# do1.net
KiCad netlist of a schematic drawn in Altium Designer
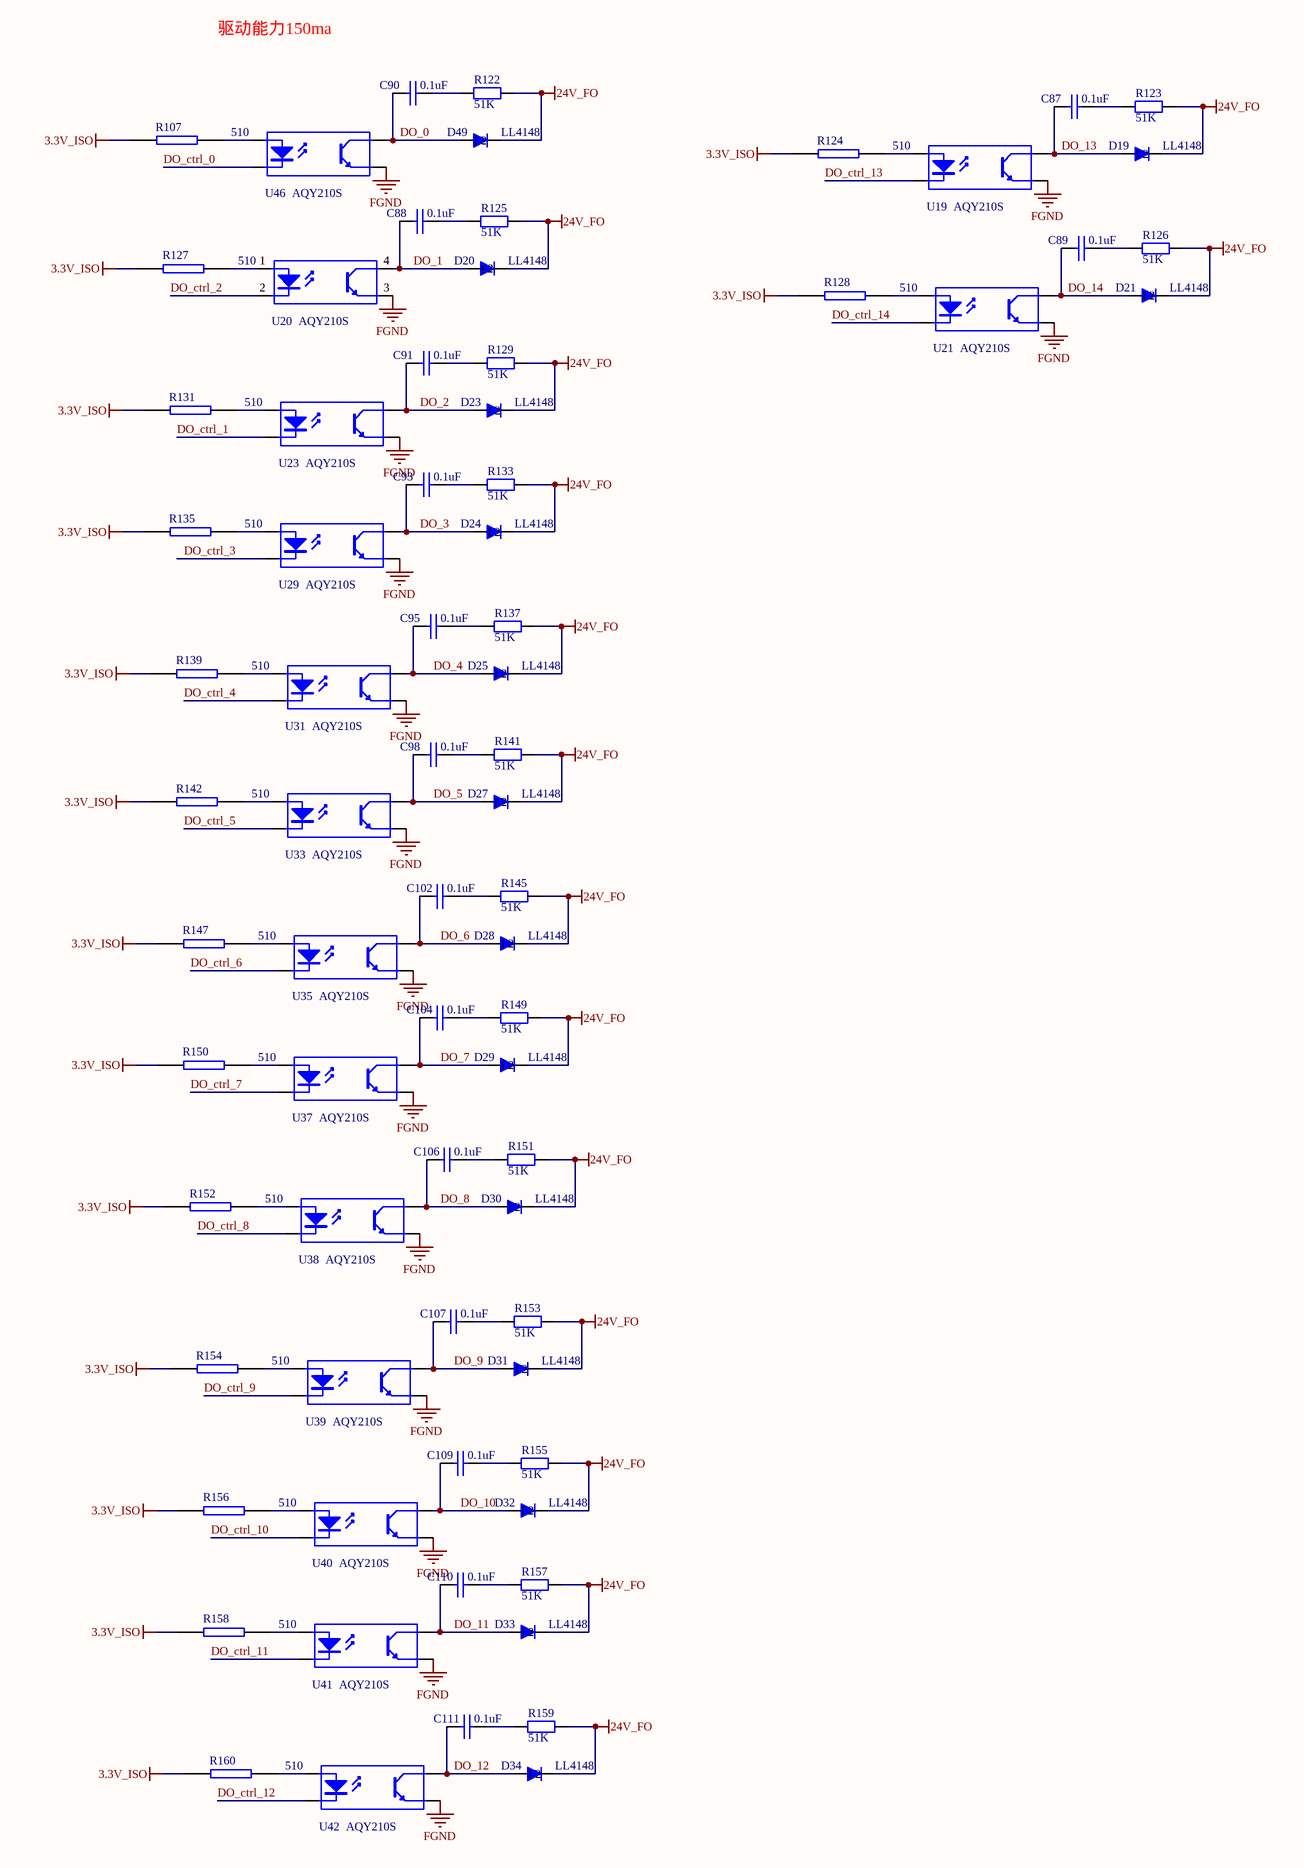
[diagram p0: do1.SchDoc]

(export (version "E")
  (design (tool "Eeschema 10.0.6"))
  (components
    (comp (ref "C87")
      (value "0.1uF")
      (footprint "0603C")
      (description "Capacitor")
      (libsource (lib "*") (part "CAP"))
    )
    (comp (ref "C88")
      (value "0.1uF")
      (footprint "0603C")
      (description "Capacitor")
      (libsource (lib "*") (part "CAP"))
    )
    (comp (ref "C89")
      (value "0.1uF")
      (footprint "0603C")
      (description "Capacitor")
      (libsource (lib "*") (part "CAP"))
    )
    (comp (ref "C90")
      (value "0.1uF")
      (footprint "0603C")
      (description "Capacitor")
      (libsource (lib "*") (part "CAP"))
    )
    (comp (ref "C91")
      (value "0.1uF")
      (footprint "0603C")
      (description "Capacitor")
      (libsource (lib "*") (part "CAP"))
    )
    (comp (ref "C93")
      (value "0.1uF")
      (footprint "0603C")
      (description "Capacitor")
      (libsource (lib "*") (part "CAP"))
    )
    (comp (ref "C95")
      (value "0.1uF")
      (footprint "0603C")
      (description "Capacitor")
      (libsource (lib "*") (part "CAP"))
    )
    (comp (ref "C98")
      (value "0.1uF")
      (footprint "0603C")
      (description "Capacitor")
      (libsource (lib "*") (part "CAP"))
    )
    (comp (ref "C102")
      (value "0.1uF")
      (footprint "0603C")
      (description "Capacitor")
      (libsource (lib "*") (part "CAP"))
    )
    (comp (ref "C104")
      (value "0.1uF")
      (footprint "0603C")
      (description "Capacitor")
      (libsource (lib "*") (part "CAP"))
    )
    (comp (ref "C106")
      (value "0.1uF")
      (footprint "0603C")
      (description "Capacitor")
      (libsource (lib "*") (part "CAP"))
    )
    (comp (ref "C107")
      (value "0.1uF")
      (footprint "0603C")
      (description "Capacitor")
      (libsource (lib "*") (part "CAP"))
    )
    (comp (ref "C109")
      (value "0.1uF")
      (footprint "0603C")
      (description "Capacitor")
      (libsource (lib "*") (part "CAP"))
    )
    (comp (ref "C110")
      (value "0.1uF")
      (footprint "0603C")
      (description "Capacitor")
      (libsource (lib "*") (part "CAP"))
    )
    (comp (ref "C111")
      (value "0.1uF")
      (footprint "0603C")
      (description "Capacitor")
      (libsource (lib "*") (part "CAP"))
    )
    (comp (ref "D19")
      (value "LL4148")
      (footprint "DO-213AB/LL34/MiniMELF")
      (description "VISHAY,LL4148,圆柱体MiniMELF100V/2A,ROHS")
      (libsource (lib "Device2018") (part "LL4148"))
    )
    (comp (ref "D20")
      (value "LL4148")
      (footprint "DO-213AB/LL34/MiniMELF")
      (description "VISHAY,LL4148,圆柱体MiniMELF100V/2A,ROHS")
      (libsource (lib "Device2018") (part "LL4148"))
    )
    (comp (ref "D21")
      (value "LL4148")
      (footprint "DO-213AB/LL34/MiniMELF")
      (description "VISHAY,LL4148,圆柱体MiniMELF100V/2A,ROHS")
      (libsource (lib "Device2018") (part "LL4148"))
    )
    (comp (ref "D23")
      (value "LL4148")
      (footprint "DO-213AB/LL34/MiniMELF")
      (description "VISHAY,LL4148,圆柱体MiniMELF100V/2A,ROHS")
      (libsource (lib "Device2018") (part "LL4148"))
    )
    (comp (ref "D24")
      (value "LL4148")
      (footprint "DO-213AB/LL34/MiniMELF")
      (description "VISHAY,LL4148,圆柱体MiniMELF100V/2A,ROHS")
      (libsource (lib "Device2018") (part "LL4148"))
    )
    (comp (ref "D25")
      (value "LL4148")
      (footprint "DO-213AB/LL34/MiniMELF")
      (description "VISHAY,LL4148,圆柱体MiniMELF100V/2A,ROHS")
      (libsource (lib "Device2018") (part "LL4148"))
    )
    (comp (ref "D27")
      (value "LL4148")
      (footprint "DO-213AB/LL34/MiniMELF")
      (description "VISHAY,LL4148,圆柱体MiniMELF100V/2A,ROHS")
      (libsource (lib "Device2018") (part "LL4148"))
    )
    (comp (ref "D28")
      (value "LL4148")
      (footprint "DO-213AB/LL34/MiniMELF")
      (description "VISHAY,LL4148,圆柱体MiniMELF100V/2A,ROHS")
      (libsource (lib "Device2018") (part "LL4148"))
    )
    (comp (ref "D29")
      (value "LL4148")
      (footprint "DO-213AB/LL34/MiniMELF")
      (description "VISHAY,LL4148,圆柱体MiniMELF100V/2A,ROHS")
      (libsource (lib "Device2018") (part "LL4148"))
    )
    (comp (ref "D30")
      (value "LL4148")
      (footprint "DO-213AB/LL34/MiniMELF")
      (description "VISHAY,LL4148,圆柱体MiniMELF100V/2A,ROHS")
      (libsource (lib "Device2018") (part "LL4148"))
    )
    (comp (ref "D31")
      (value "LL4148")
      (footprint "DO-213AB/LL34/MiniMELF")
      (description "VISHAY,LL4148,圆柱体MiniMELF100V/2A,ROHS")
      (libsource (lib "Device2018") (part "LL4148"))
    )
    (comp (ref "D32")
      (value "LL4148")
      (footprint "DO-213AB/LL34/MiniMELF")
      (description "VISHAY,LL4148,圆柱体MiniMELF100V/2A,ROHS")
      (libsource (lib "Device2018") (part "LL4148"))
    )
    (comp (ref "D33")
      (value "LL4148")
      (footprint "DO-213AB/LL34/MiniMELF")
      (description "VISHAY,LL4148,圆柱体MiniMELF100V/2A,ROHS")
      (libsource (lib "Device2018") (part "LL4148"))
    )
    (comp (ref "D34")
      (value "LL4148")
      (footprint "DO-213AB/LL34/MiniMELF")
      (description "VISHAY,LL4148,圆柱体MiniMELF100V/2A,ROHS")
      (libsource (lib "Device2018") (part "LL4148"))
    )
    (comp (ref "D49")
      (value "LL4148")
      (footprint "DO-213AB/LL34/MiniMELF")
      (description "VISHAY,LL4148,圆柱体MiniMELF100V/2A,ROHS")
      (libsource (lib "Device2018") (part "LL4148"))
    )
    (comp (ref "R107") (value "510") (footprint "0603R") (libsource (lib "*") (part "RES2")))
    (comp (ref "R122") (value "51K") (footprint "0603R") (libsource (lib "MQlibrary") (part "Res0805M")))
    (comp (ref "R123") (value "51K") (footprint "0603R") (libsource (lib "MQlibrary") (part "Res0805M")))
    (comp (ref "R124") (value "510") (footprint "0603R") (libsource (lib "*") (part "RES2")))
    (comp (ref "R125") (value "51K") (footprint "0603R") (libsource (lib "MQlibrary") (part "Res0805M")))
    (comp (ref "R126") (value "51K") (footprint "0603R") (libsource (lib "MQlibrary") (part "Res0805M")))
    (comp (ref "R127") (value "510") (footprint "0603R") (libsource (lib "*") (part "RES2")))
    (comp (ref "R128") (value "510") (footprint "0603R") (libsource (lib "*") (part "RES2")))
    (comp (ref "R129") (value "51K") (footprint "0603R") (libsource (lib "MQlibrary") (part "Res0805M")))
    (comp (ref "R131") (value "510") (footprint "0603R") (libsource (lib "*") (part "RES2")))
    (comp (ref "R133") (value "51K") (footprint "0603R") (libsource (lib "MQlibrary") (part "Res0805M")))
    (comp (ref "R135") (value "510") (footprint "0603R") (libsource (lib "*") (part "RES2")))
    (comp (ref "R137") (value "51K") (footprint "0603R") (libsource (lib "MQlibrary") (part "Res0805M")))
    (comp (ref "R139") (value "510") (footprint "0603R") (libsource (lib "*") (part "RES2")))
    (comp (ref "R141") (value "51K") (footprint "0603R") (libsource (lib "MQlibrary") (part "Res0805M")))
    (comp (ref "R142") (value "510") (footprint "0603R") (libsource (lib "*") (part "RES2")))
    (comp (ref "R145") (value "51K") (footprint "0603R") (libsource (lib "MQlibrary") (part "Res0805M")))
    (comp (ref "R147") (value "510") (footprint "0603R") (libsource (lib "*") (part "RES2")))
    (comp (ref "R149") (value "51K") (footprint "0603R") (libsource (lib "MQlibrary") (part "Res0805M")))
    (comp (ref "R150") (value "510") (footprint "0603R") (libsource (lib "*") (part "RES2")))
    (comp (ref "R151") (value "51K") (footprint "0603R") (libsource (lib "MQlibrary") (part "Res0805M")))
    (comp (ref "R152") (value "510") (footprint "0603R") (libsource (lib "*") (part "RES2")))
    (comp (ref "R153") (value "51K") (footprint "0603R") (libsource (lib "MQlibrary") (part "Res0805M")))
    (comp (ref "R154") (value "510") (footprint "0603R") (libsource (lib "*") (part "RES2")))
    (comp (ref "R155") (value "51K") (footprint "0603R") (libsource (lib "MQlibrary") (part "Res0805M")))
    (comp (ref "R156") (value "510") (footprint "0603R") (libsource (lib "*") (part "RES2")))
    (comp (ref "R157") (value "51K") (footprint "0603R") (libsource (lib "MQlibrary") (part "Res0805M")))
    (comp (ref "R158") (value "510") (footprint "0603R") (libsource (lib "*") (part "RES2")))
    (comp (ref "R159") (value "51K") (footprint "0603R") (libsource (lib "MQlibrary") (part "Res0805M")))
    (comp (ref "R160") (value "510") (footprint "0603R") (libsource (lib "*") (part "RES2")))
    (comp (ref "U19")
      (value "AQY210S")
      (footprint "sop4")
      (description "4-Pin Phototransistor Optocoupler")
      (fields (field (name "PUBLISHER") "Altium Limited"))
      (libsource (lib "") (part "Optoisolator1_1"))
    )
    (comp (ref "U20")
      (value "AQY210S")
      (footprint "sop4")
      (description "4-Pin Phototransistor Optocoupler")
      (fields (field (name "PUBLISHER") "Altium Limited"))
      (libsource (lib "Miscellaneous Devices") (part "Optoisolator1"))
    )
    (comp (ref "U21")
      (value "AQY210S")
      (footprint "sop4")
      (description "4-Pin Phototransistor Optocoupler")
      (fields (field (name "PUBLISHER") "Altium Limited"))
      (libsource (lib "") (part "Optoisolator1_1"))
    )
    (comp (ref "U23")
      (value "AQY210S")
      (footprint "sop4")
      (description "4-Pin Phototransistor Optocoupler")
      (fields (field (name "PUBLISHER") "Altium Limited"))
      (libsource (lib "") (part "Optoisolator1_1"))
    )
    (comp (ref "U29")
      (value "AQY210S")
      (footprint "sop4")
      (description "4-Pin Phototransistor Optocoupler")
      (fields (field (name "PUBLISHER") "Altium Limited"))
      (libsource (lib "") (part "Optoisolator1_1"))
    )
    (comp (ref "U31")
      (value "AQY210S")
      (footprint "sop4")
      (description "4-Pin Phototransistor Optocoupler")
      (fields (field (name "PUBLISHER") "Altium Limited"))
      (libsource (lib "") (part "Optoisolator1_1"))
    )
    (comp (ref "U33")
      (value "AQY210S")
      (footprint "sop4")
      (description "4-Pin Phototransistor Optocoupler")
      (fields (field (name "PUBLISHER") "Altium Limited"))
      (libsource (lib "") (part "Optoisolator1_1"))
    )
    (comp (ref "U35")
      (value "AQY210S")
      (footprint "sop4")
      (description "4-Pin Phototransistor Optocoupler")
      (fields (field (name "PUBLISHER") "Altium Limited"))
      (libsource (lib "") (part "Optoisolator1_1"))
    )
    (comp (ref "U37")
      (value "AQY210S")
      (footprint "sop4")
      (description "4-Pin Phototransistor Optocoupler")
      (fields (field (name "PUBLISHER") "Altium Limited"))
      (libsource (lib "") (part "Optoisolator1_1"))
    )
    (comp (ref "U38")
      (value "AQY210S")
      (footprint "sop4")
      (description "4-Pin Phototransistor Optocoupler")
      (fields (field (name "PUBLISHER") "Altium Limited"))
      (libsource (lib "") (part "Optoisolator1_1"))
    )
    (comp (ref "U39")
      (value "AQY210S")
      (footprint "sop4")
      (description "4-Pin Phototransistor Optocoupler")
      (fields (field (name "PUBLISHER") "Altium Limited"))
      (libsource (lib "") (part "Optoisolator1_1"))
    )
    (comp (ref "U40")
      (value "AQY210S")
      (footprint "sop4")
      (description "4-Pin Phototransistor Optocoupler")
      (fields (field (name "PUBLISHER") "Altium Limited"))
      (libsource (lib "") (part "Optoisolator1_1"))
    )
    (comp (ref "U41")
      (value "AQY210S")
      (footprint "sop4")
      (description "4-Pin Phototransistor Optocoupler")
      (fields (field (name "PUBLISHER") "Altium Limited"))
      (libsource (lib "") (part "Optoisolator1_1"))
    )
    (comp (ref "U42")
      (value "AQY210S")
      (footprint "sop4")
      (description "4-Pin Phototransistor Optocoupler")
      (fields (field (name "PUBLISHER") "Altium Limited"))
      (libsource (lib "") (part "Optoisolator1_1"))
    )
    (comp (ref "U46")
      (value "AQY210S")
      (footprint "sop4")
      (description "4-Pin Phototransistor Optocoupler")
      (fields (field (name "PUBLISHER") "Altium Limited"))
      (libsource (lib "") (part "Optoisolator1_1"))
    )
  )
  (nets
    (net (code "1") (name "/DO_0") (class "Default")
      (node (ref "C90") (pin "1") (pinfunction "1_1") (pintype "passive"))
      (node (ref "D49") (pin "1") (pinfunction "2_1") (pintype "passive"))
      (node (ref "U46") (pin "4") (pinfunction "C_4") (pintype "passive"))
    )
    (net (code "2") (name "/DO_1") (class "Default")
      (node (ref "C88") (pin "1") (pinfunction "1_1") (pintype "passive"))
      (node (ref "D20") (pin "1") (pinfunction "2_1") (pintype "passive"))
      (node (ref "U20") (pin "4") (pinfunction "C_4") (pintype "passive"))
    )
    (net (code "3") (name "/DO_2") (class "Default")
      (node (ref "C91") (pin "1") (pinfunction "1_1") (pintype "passive"))
      (node (ref "D23") (pin "1") (pinfunction "2_1") (pintype "passive"))
      (node (ref "U23") (pin "4") (pinfunction "C_4") (pintype "passive"))
    )
    (net (code "4") (name "/DO_3") (class "Default")
      (node (ref "C93") (pin "1") (pinfunction "1_1") (pintype "passive"))
      (node (ref "D24") (pin "1") (pinfunction "2_1") (pintype "passive"))
      (node (ref "U29") (pin "4") (pinfunction "C_4") (pintype "passive"))
    )
    (net (code "5") (name "/DO_4") (class "Default")
      (node (ref "C95") (pin "1") (pinfunction "1_1") (pintype "passive"))
      (node (ref "D25") (pin "1") (pinfunction "2_1") (pintype "passive"))
      (node (ref "U31") (pin "4") (pinfunction "C_4") (pintype "passive"))
    )
    (net (code "6") (name "/DO_5") (class "Default")
      (node (ref "C98") (pin "1") (pinfunction "1_1") (pintype "passive"))
      (node (ref "D27") (pin "1") (pinfunction "2_1") (pintype "passive"))
      (node (ref "U33") (pin "4") (pinfunction "C_4") (pintype "passive"))
    )
    (net (code "7") (name "/DO_6") (class "Default")
      (node (ref "C102") (pin "1") (pinfunction "1_1") (pintype "passive"))
      (node (ref "D28") (pin "1") (pinfunction "2_1") (pintype "passive"))
      (node (ref "U35") (pin "4") (pinfunction "C_4") (pintype "passive"))
    )
    (net (code "8") (name "/DO_7") (class "Default")
      (node (ref "C104") (pin "1") (pinfunction "1_1") (pintype "passive"))
      (node (ref "D29") (pin "1") (pinfunction "2_1") (pintype "passive"))
      (node (ref "U37") (pin "4") (pinfunction "C_4") (pintype "passive"))
    )
    (net (code "9") (name "/DO_8") (class "Default")
      (node (ref "C106") (pin "1") (pinfunction "1_1") (pintype "passive"))
      (node (ref "D30") (pin "1") (pinfunction "2_1") (pintype "passive"))
      (node (ref "U38") (pin "4") (pinfunction "C_4") (pintype "passive"))
    )
    (net (code "10") (name "/DO_9") (class "Default")
      (node (ref "C107") (pin "1") (pinfunction "1_1") (pintype "passive"))
      (node (ref "D31") (pin "1") (pinfunction "2_1") (pintype "passive"))
      (node (ref "U39") (pin "4") (pinfunction "C_4") (pintype "passive"))
    )
    (net (code "11") (name "/DO_10") (class "Default")
      (node (ref "C109") (pin "1") (pinfunction "1_1") (pintype "passive"))
      (node (ref "D32") (pin "1") (pinfunction "2_1") (pintype "passive"))
      (node (ref "U40") (pin "4") (pinfunction "C_4") (pintype "passive"))
    )
    (net (code "12") (name "/DO_11") (class "Default")
      (node (ref "C110") (pin "1") (pinfunction "1_1") (pintype "passive"))
      (node (ref "D33") (pin "1") (pinfunction "2_1") (pintype "passive"))
      (node (ref "U41") (pin "4") (pinfunction "C_4") (pintype "passive"))
    )
    (net (code "13") (name "/DO_12") (class "Default")
      (node (ref "C111") (pin "1") (pinfunction "1_1") (pintype "passive"))
      (node (ref "D34") (pin "1") (pinfunction "2_1") (pintype "passive"))
      (node (ref "U42") (pin "4") (pinfunction "C_4") (pintype "passive"))
    )
    (net (code "14") (name "/DO_13") (class "Default")
      (node (ref "C87") (pin "1") (pinfunction "1_1") (pintype "passive"))
      (node (ref "D19") (pin "1") (pinfunction "2_1") (pintype "passive"))
      (node (ref "U19") (pin "4") (pinfunction "C_4") (pintype "passive"))
    )
    (net (code "15") (name "/DO_14") (class "Default")
      (node (ref "C89") (pin "1") (pinfunction "1_1") (pintype "passive"))
      (node (ref "D21") (pin "1") (pinfunction "2_1") (pintype "passive"))
      (node (ref "U21") (pin "4") (pinfunction "C_4") (pintype "passive"))
    )
    (net (code "16") (name "/DO_ctrl_0") (class "Default")
      (node (ref "U46") (pin "2") (pinfunction "K_2") (pintype "passive"))
    )
    (net (code "17") (name "/DO_ctrl_1") (class "Default")
      (node (ref "U23") (pin "2") (pinfunction "K_2") (pintype "passive"))
    )
    (net (code "18") (name "/DO_ctrl_2") (class "Default")
      (node (ref "U20") (pin "2") (pinfunction "K_2") (pintype "passive"))
    )
    (net (code "19") (name "/DO_ctrl_3") (class "Default")
      (node (ref "U29") (pin "2") (pinfunction "K_2") (pintype "passive"))
    )
    (net (code "20") (name "/DO_ctrl_4") (class "Default")
      (node (ref "U31") (pin "2") (pinfunction "K_2") (pintype "passive"))
    )
    (net (code "21") (name "/DO_ctrl_5") (class "Default")
      (node (ref "U33") (pin "2") (pinfunction "K_2") (pintype "passive"))
    )
    (net (code "22") (name "/DO_ctrl_6") (class "Default")
      (node (ref "U35") (pin "2") (pinfunction "K_2") (pintype "passive"))
    )
    (net (code "23") (name "/DO_ctrl_7") (class "Default")
      (node (ref "U37") (pin "2") (pinfunction "K_2") (pintype "passive"))
    )
    (net (code "24") (name "/DO_ctrl_8") (class "Default")
      (node (ref "U38") (pin "2") (pinfunction "K_2") (pintype "passive"))
    )
    (net (code "25") (name "/DO_ctrl_9") (class "Default")
      (node (ref "U39") (pin "2") (pinfunction "K_2") (pintype "passive"))
    )
    (net (code "26") (name "/DO_ctrl_10") (class "Default")
      (node (ref "U40") (pin "2") (pinfunction "K_2") (pintype "passive"))
    )
    (net (code "27") (name "/DO_ctrl_11") (class "Default")
      (node (ref "U41") (pin "2") (pinfunction "K_2") (pintype "passive"))
    )
    (net (code "28") (name "/DO_ctrl_12") (class "Default")
      (node (ref "U42") (pin "2") (pinfunction "K_2") (pintype "passive"))
    )
    (net (code "29") (name "/DO_ctrl_13") (class "Default")
      (node (ref "U19") (pin "2") (pinfunction "K_2") (pintype "passive"))
    )
    (net (code "30") (name "/DO_ctrl_14") (class "Default")
      (node (ref "U21") (pin "2") (pinfunction "K_2") (pintype "passive"))
    )
    (net (code "31") (name "3.3V_ISO") (class "Default")
      (node (ref "R107") (pin "2") (pinfunction "2_2") (pintype "passive"))
      (node (ref "R124") (pin "2") (pinfunction "2_2") (pintype "passive"))
      (node (ref "R127") (pin "2") (pinfunction "2_2") (pintype "passive"))
      (node (ref "R128") (pin "2") (pinfunction "2_2") (pintype "passive"))
      (node (ref "R131") (pin "2") (pinfunction "2_2") (pintype "passive"))
      (node (ref "R135") (pin "2") (pinfunction "2_2") (pintype "passive"))
      (node (ref "R139") (pin "2") (pinfunction "2_2") (pintype "passive"))
      (node (ref "R142") (pin "2") (pinfunction "2_2") (pintype "passive"))
      (node (ref "R147") (pin "2") (pinfunction "2_2") (pintype "passive"))
      (node (ref "R150") (pin "2") (pinfunction "2_2") (pintype "passive"))
      (node (ref "R152") (pin "2") (pinfunction "2_2") (pintype "passive"))
      (node (ref "R154") (pin "2") (pinfunction "2_2") (pintype "passive"))
      (node (ref "R156") (pin "2") (pinfunction "2_2") (pintype "passive"))
      (node (ref "R158") (pin "2") (pinfunction "2_2") (pintype "passive"))
      (node (ref "R160") (pin "2") (pinfunction "2_2") (pintype "passive"))
    )
    (net (code "32") (name "24V_FO") (class "Default")
      (node (ref "D19") (pin "2") (pinfunction "1_2") (pintype "passive"))
      (node (ref "D20") (pin "2") (pinfunction "1_2") (pintype "passive"))
      (node (ref "D21") (pin "2") (pinfunction "1_2") (pintype "passive"))
      (node (ref "D23") (pin "2") (pinfunction "1_2") (pintype "passive"))
      (node (ref "D24") (pin "2") (pinfunction "1_2") (pintype "passive"))
      (node (ref "D25") (pin "2") (pinfunction "1_2") (pintype "passive"))
      (node (ref "D27") (pin "2") (pinfunction "1_2") (pintype "passive"))
      (node (ref "D28") (pin "2") (pinfunction "1_2") (pintype "passive"))
      (node (ref "D29") (pin "2") (pinfunction "1_2") (pintype "passive"))
      (node (ref "D30") (pin "2") (pinfunction "1_2") (pintype "passive"))
      (node (ref "D31") (pin "2") (pinfunction "1_2") (pintype "passive"))
      (node (ref "D32") (pin "2") (pinfunction "1_2") (pintype "passive"))
      (node (ref "D33") (pin "2") (pinfunction "1_2") (pintype "passive"))
      (node (ref "D34") (pin "2") (pinfunction "1_2") (pintype "passive"))
      (node (ref "D49") (pin "2") (pinfunction "1_2") (pintype "passive"))
      (node (ref "R122") (pin "2") (pinfunction "2_2") (pintype "passive"))
      (node (ref "R123") (pin "2") (pinfunction "2_2") (pintype "passive"))
      (node (ref "R125") (pin "2") (pinfunction "2_2") (pintype "passive"))
      (node (ref "R126") (pin "2") (pinfunction "2_2") (pintype "passive"))
      (node (ref "R129") (pin "2") (pinfunction "2_2") (pintype "passive"))
      (node (ref "R133") (pin "2") (pinfunction "2_2") (pintype "passive"))
      (node (ref "R137") (pin "2") (pinfunction "2_2") (pintype "passive"))
      (node (ref "R141") (pin "2") (pinfunction "2_2") (pintype "passive"))
      (node (ref "R145") (pin "2") (pinfunction "2_2") (pintype "passive"))
      (node (ref "R149") (pin "2") (pinfunction "2_2") (pintype "passive"))
      (node (ref "R151") (pin "2") (pinfunction "2_2") (pintype "passive"))
      (node (ref "R153") (pin "2") (pinfunction "2_2") (pintype "passive"))
      (node (ref "R155") (pin "2") (pinfunction "2_2") (pintype "passive"))
      (node (ref "R157") (pin "2") (pinfunction "2_2") (pintype "passive"))
      (node (ref "R159") (pin "2") (pinfunction "2_2") (pintype "passive"))
    )
    (net (code "33") (name "FGND") (class "Default")
      (node (ref "U19") (pin "3") (pinfunction "E_3") (pintype "passive"))
      (node (ref "U20") (pin "3") (pinfunction "E_3") (pintype "passive"))
      (node (ref "U21") (pin "3") (pinfunction "E_3") (pintype "passive"))
      (node (ref "U23") (pin "3") (pinfunction "E_3") (pintype "passive"))
      (node (ref "U29") (pin "3") (pinfunction "E_3") (pintype "passive"))
      (node (ref "U31") (pin "3") (pinfunction "E_3") (pintype "passive"))
      (node (ref "U33") (pin "3") (pinfunction "E_3") (pintype "passive"))
      (node (ref "U35") (pin "3") (pinfunction "E_3") (pintype "passive"))
      (node (ref "U37") (pin "3") (pinfunction "E_3") (pintype "passive"))
      (node (ref "U38") (pin "3") (pinfunction "E_3") (pintype "passive"))
      (node (ref "U39") (pin "3") (pinfunction "E_3") (pintype "passive"))
      (node (ref "U40") (pin "3") (pinfunction "E_3") (pintype "passive"))
      (node (ref "U41") (pin "3") (pinfunction "E_3") (pintype "passive"))
      (node (ref "U42") (pin "3") (pinfunction "E_3") (pintype "passive"))
      (node (ref "U46") (pin "3") (pinfunction "E_3") (pintype "passive"))
    )
    (net (code "34") (name "Net-(C87-Pad2)") (class "Default")
      (node (ref "C87") (pin "2") (pinfunction "2_2") (pintype "passive"))
      (node (ref "R123") (pin "1") (pinfunction "1_1") (pintype "passive"))
    )
    (net (code "35") (name "Net-(C88-Pad2)") (class "Default")
      (node (ref "C88") (pin "2") (pinfunction "2_2") (pintype "passive"))
      (node (ref "R125") (pin "1") (pinfunction "1_1") (pintype "passive"))
    )
    (net (code "36") (name "Net-(C89-Pad2)") (class "Default")
      (node (ref "C89") (pin "2") (pinfunction "2_2") (pintype "passive"))
      (node (ref "R126") (pin "1") (pinfunction "1_1") (pintype "passive"))
    )
    (net (code "37") (name "Net-(C90-Pad2)") (class "Default")
      (node (ref "C90") (pin "2") (pinfunction "2_2") (pintype "passive"))
      (node (ref "R122") (pin "1") (pinfunction "1_1") (pintype "passive"))
    )
    (net (code "38") (name "Net-(C91-Pad2)") (class "Default")
      (node (ref "C91") (pin "2") (pinfunction "2_2") (pintype "passive"))
      (node (ref "R129") (pin "1") (pinfunction "1_1") (pintype "passive"))
    )
    (net (code "39") (name "Net-(C93-Pad2)") (class "Default")
      (node (ref "C93") (pin "2") (pinfunction "2_2") (pintype "passive"))
      (node (ref "R133") (pin "1") (pinfunction "1_1") (pintype "passive"))
    )
    (net (code "40") (name "Net-(C95-Pad2)") (class "Default")
      (node (ref "C95") (pin "2") (pinfunction "2_2") (pintype "passive"))
      (node (ref "R137") (pin "1") (pinfunction "1_1") (pintype "passive"))
    )
    (net (code "41") (name "Net-(C98-Pad2)") (class "Default")
      (node (ref "C98") (pin "2") (pinfunction "2_2") (pintype "passive"))
      (node (ref "R141") (pin "1") (pinfunction "1_1") (pintype "passive"))
    )
    (net (code "42") (name "Net-(C102-Pad2)") (class "Default")
      (node (ref "C102") (pin "2") (pinfunction "2_2") (pintype "passive"))
      (node (ref "R145") (pin "1") (pinfunction "1_1") (pintype "passive"))
    )
    (net (code "43") (name "Net-(C104-Pad2)") (class "Default")
      (node (ref "C104") (pin "2") (pinfunction "2_2") (pintype "passive"))
      (node (ref "R149") (pin "1") (pinfunction "1_1") (pintype "passive"))
    )
    (net (code "44") (name "Net-(C106-Pad2)") (class "Default")
      (node (ref "C106") (pin "2") (pinfunction "2_2") (pintype "passive"))
      (node (ref "R151") (pin "1") (pinfunction "1_1") (pintype "passive"))
    )
    (net (code "45") (name "Net-(C107-Pad2)") (class "Default")
      (node (ref "C107") (pin "2") (pinfunction "2_2") (pintype "passive"))
      (node (ref "R153") (pin "1") (pinfunction "1_1") (pintype "passive"))
    )
    (net (code "46") (name "Net-(C109-Pad2)") (class "Default")
      (node (ref "C109") (pin "2") (pinfunction "2_2") (pintype "passive"))
      (node (ref "R155") (pin "1") (pinfunction "1_1") (pintype "passive"))
    )
    (net (code "47") (name "Net-(C110-Pad2)") (class "Default")
      (node (ref "C110") (pin "2") (pinfunction "2_2") (pintype "passive"))
      (node (ref "R157") (pin "1") (pinfunction "1_1") (pintype "passive"))
    )
    (net (code "48") (name "Net-(C111-Pad2)") (class "Default")
      (node (ref "C111") (pin "2") (pinfunction "2_2") (pintype "passive"))
      (node (ref "R159") (pin "1") (pinfunction "1_1") (pintype "passive"))
    )
    (net (code "49") (name "Net-(U19-A)") (class "Default")
      (node (ref "R124") (pin "1") (pinfunction "1_1") (pintype "passive"))
      (node (ref "U19") (pin "1") (pinfunction "A_1") (pintype "passive"))
    )
    (net (code "50") (name "Net-(U20-A)") (class "Default")
      (node (ref "R127") (pin "1") (pinfunction "1_1") (pintype "passive"))
      (node (ref "U20") (pin "1") (pinfunction "A_1") (pintype "passive"))
    )
    (net (code "51") (name "Net-(U21-A)") (class "Default")
      (node (ref "R128") (pin "1") (pinfunction "1_1") (pintype "passive"))
      (node (ref "U21") (pin "1") (pinfunction "A_1") (pintype "passive"))
    )
    (net (code "52") (name "Net-(U23-A)") (class "Default")
      (node (ref "R131") (pin "1") (pinfunction "1_1") (pintype "passive"))
      (node (ref "U23") (pin "1") (pinfunction "A_1") (pintype "passive"))
    )
    (net (code "53") (name "Net-(U29-A)") (class "Default")
      (node (ref "R135") (pin "1") (pinfunction "1_1") (pintype "passive"))
      (node (ref "U29") (pin "1") (pinfunction "A_1") (pintype "passive"))
    )
    (net (code "54") (name "Net-(U31-A)") (class "Default")
      (node (ref "R139") (pin "1") (pinfunction "1_1") (pintype "passive"))
      (node (ref "U31") (pin "1") (pinfunction "A_1") (pintype "passive"))
    )
    (net (code "55") (name "Net-(U33-A)") (class "Default")
      (node (ref "R142") (pin "1") (pinfunction "1_1") (pintype "passive"))
      (node (ref "U33") (pin "1") (pinfunction "A_1") (pintype "passive"))
    )
    (net (code "56") (name "Net-(U35-A)") (class "Default")
      (node (ref "R147") (pin "1") (pinfunction "1_1") (pintype "passive"))
      (node (ref "U35") (pin "1") (pinfunction "A_1") (pintype "passive"))
    )
    (net (code "57") (name "Net-(U37-A)") (class "Default")
      (node (ref "R150") (pin "1") (pinfunction "1_1") (pintype "passive"))
      (node (ref "U37") (pin "1") (pinfunction "A_1") (pintype "passive"))
    )
    (net (code "58") (name "Net-(U38-A)") (class "Default")
      (node (ref "R152") (pin "1") (pinfunction "1_1") (pintype "passive"))
      (node (ref "U38") (pin "1") (pinfunction "A_1") (pintype "passive"))
    )
    (net (code "59") (name "Net-(U39-A)") (class "Default")
      (node (ref "R154") (pin "1") (pinfunction "1_1") (pintype "passive"))
      (node (ref "U39") (pin "1") (pinfunction "A_1") (pintype "passive"))
    )
    (net (code "60") (name "Net-(U40-A)") (class "Default")
      (node (ref "R156") (pin "1") (pinfunction "1_1") (pintype "passive"))
      (node (ref "U40") (pin "1") (pinfunction "A_1") (pintype "passive"))
    )
    (net (code "61") (name "Net-(U41-A)") (class "Default")
      (node (ref "R158") (pin "1") (pinfunction "1_1") (pintype "passive"))
      (node (ref "U41") (pin "1") (pinfunction "A_1") (pintype "passive"))
    )
    (net (code "62") (name "Net-(U42-A)") (class "Default")
      (node (ref "R160") (pin "1") (pinfunction "1_1") (pintype "passive"))
      (node (ref "U42") (pin "1") (pinfunction "A_1") (pintype "passive"))
    )
    (net (code "63") (name "Net-(U46-A)") (class "Default")
      (node (ref "R107") (pin "1") (pinfunction "1_1") (pintype "passive"))
      (node (ref "U46") (pin "1") (pinfunction "A_1") (pintype "passive"))
    )
  )
)
